# Battery_Mgmt_Sys_-_AMS.net
KiCad netlist of a schematic drawn in Altium Designer
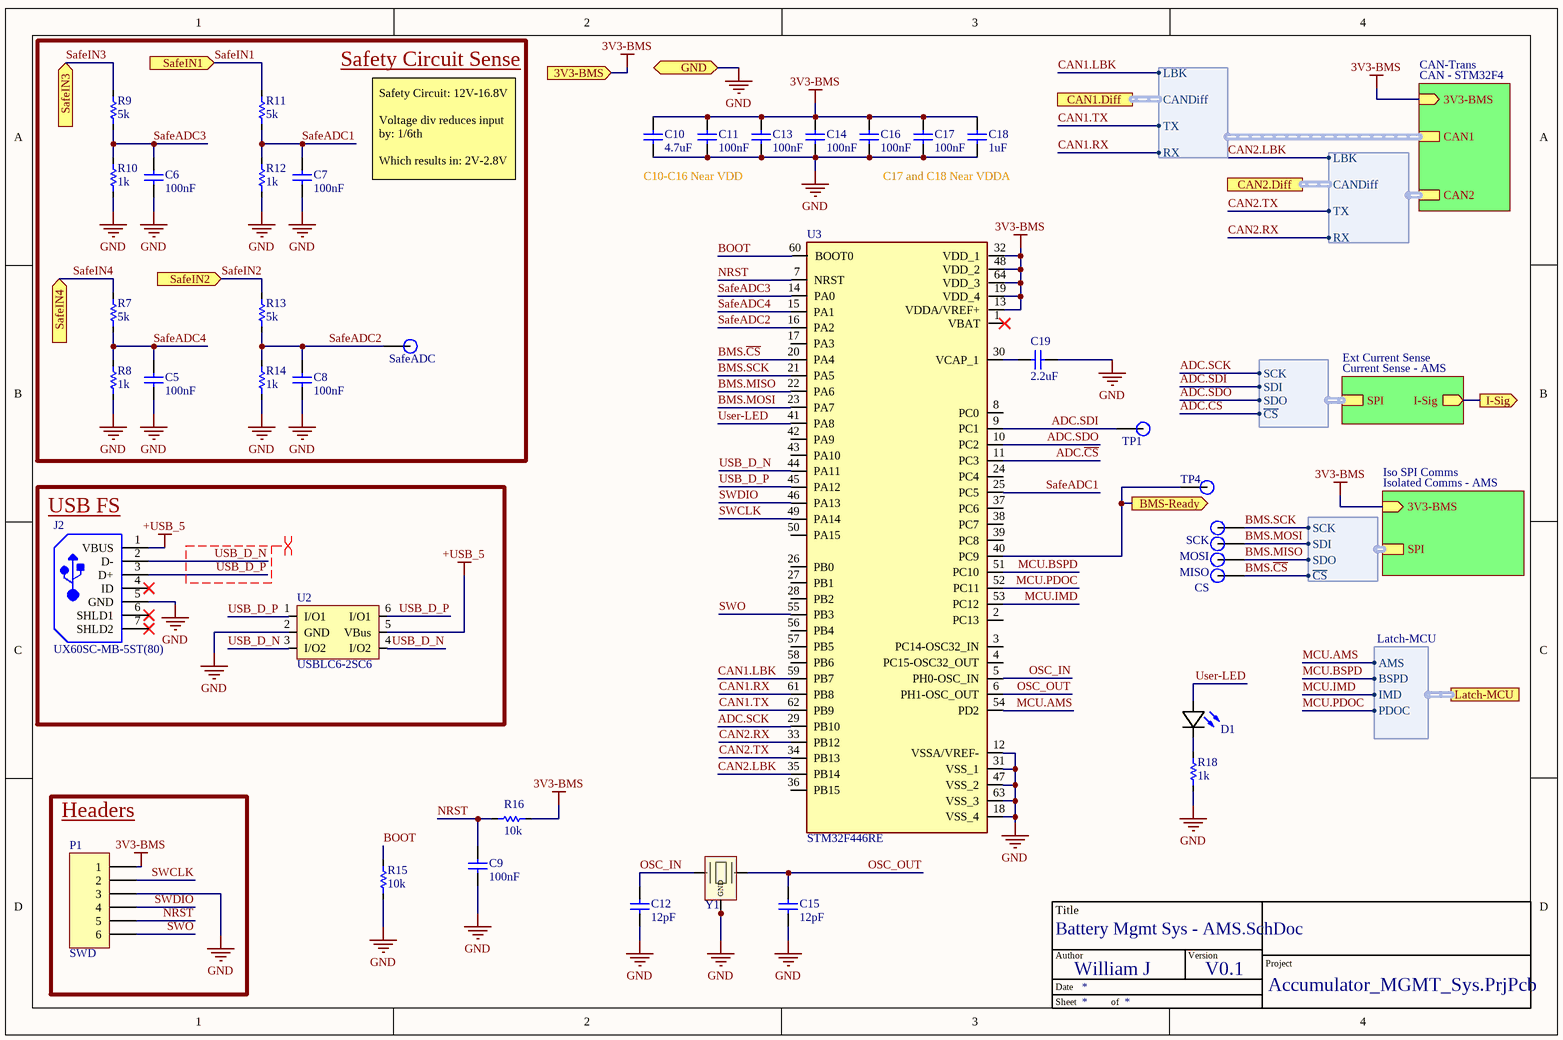
[diagram p0: Battery Mgmt Sys - AMS.SchDoc]

(export (version "E")
  (design (tool "Eeschema 10.0.6"))
  (components
    (comp (ref "C5")
      (value "100nF")
      (footprint "C_0603")
      (description "Capacitor")
      (fields (field (name "Comment") "C0603C104K3RAC7013"))
      (libsource (lib "Passives") (part "Capacitor"))
    )
    (comp (ref "C6")
      (value "100nF")
      (footprint "C_0603")
      (description "Capacitor")
      (fields (field (name "Comment") "C0603C104K3RAC7013"))
      (libsource (lib "Passives") (part "Capacitor"))
    )
    (comp (ref "C7")
      (value "100nF")
      (footprint "C_0603")
      (description "Capacitor")
      (fields (field (name "Comment") "C0603C104K3RAC7013"))
      (libsource (lib "Passives") (part "Capacitor"))
    )
    (comp (ref "C8")
      (value "100nF")
      (footprint "C_0603")
      (description "Capacitor")
      (fields (field (name "Comment") "C0603C104K3RAC7013"))
      (libsource (lib "Passives") (part "Capacitor"))
    )
    (comp (ref "C9")
      (value "100nF")
      (footprint "C_0603")
      (description "Capacitor")
      (fields (field (name "Comment") "C0603C104K3RAC7013"))
      (libsource (lib "Passives") (part "Capacitor"))
    )
    (comp (ref "C10")
      (value "4.7uF")
      (footprint "C_0603")
      (description "Capacitor")
      (fields (field (name "Comment") "CL10A475KP8NNNL"))
      (libsource (lib "Passives") (part "Capacitor"))
    )
    (comp (ref "C11")
      (value "100nF")
      (footprint "C_0603")
      (description "Capacitor")
      (fields (field (name "Comment") "C0603C104K3RAC7013"))
      (libsource (lib "Passives") (part "Capacitor"))
    )
    (comp (ref "C12")
      (value "12pF")
      (footprint "0402")
      (description "Capacitor")
      (fields (field (name "Comment") "GCM1555C1H120FA16D"))
      (libsource (lib "Passives") (part "Capacitor"))
    )
    (comp (ref "C13")
      (value "100nF")
      (footprint "C_0603")
      (description "Capacitor")
      (fields (field (name "Comment") "C0603C104K3RAC7013"))
      (libsource (lib "Passives") (part "Capacitor"))
    )
    (comp (ref "C14")
      (value "100nF")
      (footprint "C_0603")
      (description "Capacitor")
      (fields (field (name "Comment") "C0603C104K3RAC7013"))
      (libsource (lib "Passives") (part "Capacitor"))
    )
    (comp (ref "C15")
      (value "12pF")
      (footprint "0402")
      (description "Capacitor")
      (fields (field (name "Comment") "GCM1555C1H120FA16D"))
      (libsource (lib "Passives") (part "Capacitor"))
    )
    (comp (ref "C16")
      (value "100nF")
      (footprint "C_0603")
      (description "Capacitor")
      (fields (field (name "Comment") "C0603C104K3RAC7013"))
      (libsource (lib "Passives") (part "Capacitor"))
    )
    (comp (ref "C17")
      (value "100nF")
      (footprint "C_0603")
      (description "Capacitor")
      (fields (field (name "Comment") "C0603C104K3RAC7013"))
      (libsource (lib "Passives") (part "Capacitor"))
    )
    (comp (ref "C18")
      (value "1uF")
      (footprint "C_0603")
      (description "Capacitor")
      (fields (field (name "Comment") "CL10A105KP8NNNL"))
      (libsource (lib "Passives") (part "Capacitor"))
    )
    (comp (ref "C19")
      (value "2.2uF")
      (footprint "C_0603")
      (description "Capacitor")
      (fields (field (name "Comment") "CL10A225KP8NNNC"))
      (libsource (lib "Passives") (part "Capacitor"))
    )
    (comp (ref "CS")
      (value "Test Point")
      (footprint "Test Point")
      (description "1.2mm Test point")
      (libsource (lib "PCHLib") (part "Test Point"))
    )
    (comp (ref "D1")
      (value "150060BS55040")
      (footprint "LED (0603)")
      (description "LED BLUE DIFFUSED 0603 SMD")
      (fields (field (name "MANUFACTURER") "Wurth Electronics"))
      (libsource (lib "LEDLib") (part "150060BS55040"))
    )
    (comp (ref "J2")
      (value "UX60SC-MB-5ST(80)")
      (footprint "HIRO-UX60SC-MB-5ST(80)_V")
      (fields (field (name "MANUFACTURER") "Hirose Electric"))
      (libsource (lib "Altium Content Vault") (part "USB-5-2SHLD"))
    )
    (comp (ref "MISO")
      (value "Test Point")
      (footprint "Test Point")
      (description "1.2mm Test point")
      (libsource (lib "PCHLib") (part "Test Point"))
    )
    (comp (ref "MOSI")
      (value "Test Point")
      (footprint "Test Point")
      (description "1.2mm Test point")
      (libsource (lib "PCHLib") (part "Test Point"))
    )
    (comp (ref "P1")
      (value "SWD")
      (footprint "HDR1X6")
      (description "Header, 6-Pin")
      (fields (field (name "PUBLISHER") "Altium Limited"))
      (libsource (lib "Miscellaneous Connectors") (part "Header 6"))
    )
    (comp (ref "R7")
      (value "5k")
      (footprint "R-0603")
      (fields (field (name "Comment") "CR0603AFX-5101EAS"))
      (libsource (lib "Passives") (part "Resistor"))
    )
    (comp (ref "R8")
      (value "1k")
      (footprint "R-0603")
      (description "Voltage divider")
      (fields (field (name "Comment") "CR0603AFX-1001ELF"))
      (libsource (lib "Passives") (part "Resistor"))
    )
    (comp (ref "R9")
      (value "5k")
      (footprint "R-0603")
      (fields (field (name "Comment") "CR0603AFX-5101EAS"))
      (libsource (lib "Passives") (part "Resistor"))
    )
    (comp (ref "R10")
      (value "1k")
      (footprint "R-0603")
      (description "Voltage divider")
      (fields (field (name "Comment") "CR0603AFX-1001ELF"))
      (libsource (lib "Passives") (part "Resistor"))
    )
    (comp (ref "R11")
      (value "5k")
      (footprint "R-0603")
      (fields (field (name "Comment") "CR0603AFX-5101EAS"))
      (libsource (lib "Passives") (part "Resistor"))
    )
    (comp (ref "R12")
      (value "1k")
      (footprint "R-0603")
      (description "Voltage divider")
      (fields (field (name "Comment") "CR0603AFX-1001ELF"))
      (libsource (lib "Passives") (part "Resistor"))
    )
    (comp (ref "R13")
      (value "5k")
      (footprint "R-0603")
      (fields (field (name "Comment") "CR0603AFX-5101EAS"))
      (libsource (lib "Passives") (part "Resistor"))
    )
    (comp (ref "R14")
      (value "1k")
      (footprint "R-0603")
      (description "Voltage divider")
      (fields (field (name "Comment") "CR0603AFX-1001ELF"))
      (libsource (lib "Passives") (part "Resistor"))
    )
    (comp (ref "R15")
      (value "10k")
      (footprint "R-0603")
      (description "Resistor")
      (fields (field (name "Comment") "RC0603FR-1310KL"))
      (libsource (lib "Passives") (part "Resistor"))
    )
    (comp (ref "R16")
      (value "10k")
      (footprint "R-0603")
      (description "Resistor")
      (fields (field (name "Comment") "RC0603FR-1310KL"))
      (libsource (lib "Passives") (part "Resistor"))
    )
    (comp (ref "R18")
      (value "1k")
      (footprint "R-0603")
      (description "Resistor")
      (fields (field (name "Comment") "CR0603AFX-1001ELF"))
      (libsource (lib "Passives") (part "Resistor"))
    )
    (comp (ref "SafeADC")
      (value "Test Point")
      (footprint "Test Point")
      (description "1.2mm Test point")
      (libsource (lib "PCHLib") (part "Test Point"))
    )
    (comp (ref "SCK")
      (value "Test Point")
      (footprint "Test Point")
      (description "1.2mm Test point")
      (libsource (lib "PCHLib") (part "Test Point"))
    )
    (comp (ref "TP1")
      (value "Test Point")
      (footprint "Test Point")
      (description "1.2mm Test point")
      (libsource (lib "PCHLib") (part "Test Point"))
    )
    (comp (ref "TP4")
      (value "Test Point")
      (footprint "Test Point")
      (description "1.2mm Test point")
      (libsource (lib "PCHLib") (part "Test Point"))
    )
    (comp (ref "U2")
      (value "USBLC6-2SC6")
      (footprint "USBLC6-2SC6")
      (description "TVS DIODE 5.25V 17V SOT23-6")
      (fields (field (name "MANUFACTURER") "STMicroelectronics"))
      (libsource (lib "CompLib") (part "USBLC6-2SC6"))
    )
    (comp (ref "U3")
      (value "STM32F446RE")
      (footprint "QFP50P1200X1200X160-64N")
      (description "32 Bit Microcontroller, High Performance, ARM Cortex-M4, 180 MHz, 256 KB, 128 KB, 64, LQFP")
      (libsource (lib "SnapEDA_Library") (part "STM32F446RE"))
    )
    (comp (ref "Y1")
      (value "CX2016DB26000D0FLJCC")
      (footprint "CX2016DB26000D0FLJCC")
      (description "Crystals AEC-Q200 26000kHz 8pF 2x1.6mm")
      (libsource (lib "PCHLib") (part "CX2016DB26000D0FLJCC"))
    )
  )
  (nets
    (net (code "5") (name "+USB_5") (class "Default")
      (node (ref "J2") (pin "1") (pinfunction "VBUS_1") (pintype "passive"))
      (node (ref "U2") (pin "5") (pinfunction "VBus_5") (pintype "passive"))
    )
    (net (code "7") (name "/ADC.SCK") (class "Default")
      (node (ref "U3") (pin "29") (pinfunction "PB10_29") (pintype "passive"))
    )
    (net (code "8") (name "/ADC.SDI") (class "Default")
      (node (ref "TP1") (pin "1") (pinfunction "1_1") (pintype "passive"))
      (node (ref "U3") (pin "9") (pinfunction "PC1_9") (pintype "passive"))
    )
    (net (code "9") (name "/ADC.SDO") (class "Default")
      (node (ref "U3") (pin "10") (pinfunction "PC2_10") (pintype "passive"))
    )
    (net (code "10") (name "/ADC.~{CS}") (class "Default")
      (node (ref "U3") (pin "11") (pinfunction "PC3_11") (pintype "passive"))
    )
    (net (code "11") (name "/BMS-Ready") (class "Default")
      (node (ref "TP4") (pin "1") (pinfunction "1_1") (pintype "passive"))
      (node (ref "U3") (pin "40") (pinfunction "PC9_40") (pintype "passive"))
    )
    (net (code "12") (name "/BMS.MISO") (class "Default")
      (node (ref "MISO") (pin "1") (pinfunction "1_1") (pintype "passive"))
      (node (ref "U3") (pin "22") (pinfunction "PA6_22") (pintype "passive"))
    )
    (net (code "13") (name "/BMS.MOSI") (class "Default")
      (node (ref "MOSI") (pin "1") (pinfunction "1_1") (pintype "passive"))
      (node (ref "U3") (pin "23") (pinfunction "PA7_23") (pintype "passive"))
    )
    (net (code "14") (name "/BMS.SCK") (class "Default")
      (node (ref "SCK") (pin "1") (pinfunction "1_1") (pintype "passive"))
      (node (ref "U3") (pin "21") (pinfunction "PA5_21") (pintype "passive"))
    )
    (net (code "15") (name "/BMS.~{CS}") (class "Default")
      (node (ref "CS") (pin "1") (pinfunction "1_1") (pintype "passive"))
      (node (ref "U3") (pin "20") (pinfunction "PA4_20") (pintype "passive"))
    )
    (net (code "16") (name "/BOOT") (class "Default")
      (node (ref "R15") (pin "2") (pinfunction "2_2") (pintype "passive"))
      (node (ref "U3") (pin "60") (pinfunction "BOOT0_60") (pintype "passive"))
    )
    (net (code "17") (name "/CAN1.LBK") (class "Default")
      (node (ref "U3") (pin "59") (pinfunction "PB7_59") (pintype "passive"))
    )
    (net (code "18") (name "/CAN1.RX") (class "Default")
      (node (ref "U3") (pin "61") (pinfunction "PB8_61") (pintype "passive"))
    )
    (net (code "19") (name "/CAN1.TX") (class "Default")
      (node (ref "U3") (pin "62") (pinfunction "PB9_62") (pintype "passive"))
    )
    (net (code "22") (name "/CAN2.LBK") (class "Default")
      (node (ref "U3") (pin "35") (pinfunction "PB14_35") (pintype "passive"))
    )
    (net (code "23") (name "/CAN2.RX") (class "Default")
      (node (ref "U3") (pin "33") (pinfunction "PB12_33") (pintype "passive"))
    )
    (net (code "24") (name "/CAN2.TX") (class "Default")
      (node (ref "U3") (pin "34") (pinfunction "PB13_34") (pintype "passive"))
    )
    (net (code "26") (name "/MCU.AMS") (class "Default")
      (node (ref "U3") (pin "54") (pinfunction "PD2_54") (pintype "passive"))
    )
    (net (code "27") (name "/MCU.BSPD") (class "Default")
      (node (ref "U3") (pin "51") (pinfunction "PC10_51") (pintype "passive"))
    )
    (net (code "28") (name "/MCU.IMD") (class "Default")
      (node (ref "U3") (pin "53") (pinfunction "PC12_53") (pintype "passive"))
    )
    (net (code "29") (name "/MCU.PDOC") (class "Default")
      (node (ref "U3") (pin "52") (pinfunction "PC11_52") (pintype "passive"))
    )
    (net (code "30") (name "/NRST") (class "Default")
      (node (ref "C9") (pin "2") (pinfunction "2_2") (pintype "passive"))
      (node (ref "P1") (pin "5") (pinfunction "5_5") (pintype "passive"))
      (node (ref "R16") (pin "1") (pinfunction "1_1") (pintype "passive"))
      (node (ref "U3") (pin "7") (pinfunction "NRST_7") (pintype "passive"))
    )
    (net (code "31") (name "/OSC_IN") (class "Default")
      (node (ref "C12") (pin "2") (pinfunction "2_2") (pintype "passive"))
      (node (ref "U3") (pin "5") (pinfunction "PH0-OSC_IN_5") (pintype "passive"))
      (node (ref "Y1") (pin "1") (pinfunction "1_1") (pintype "passive"))
    )
    (net (code "32") (name "/OSC_OUT") (class "Default")
      (node (ref "C15") (pin "2") (pinfunction "2_2") (pintype "passive"))
      (node (ref "U3") (pin "6") (pinfunction "PH1-OSC_OUT_6") (pintype "passive"))
      (node (ref "Y1") (pin "3") (pinfunction "3_3") (pintype "passive"))
    )
    (net (code "33") (name "/SWCLK") (class "Default")
      (node (ref "P1") (pin "2") (pinfunction "2_2") (pintype "passive"))
      (node (ref "U3") (pin "49") (pinfunction "PA14_49") (pintype "passive"))
    )
    (net (code "34") (name "/SWDIO") (class "Default")
      (node (ref "P1") (pin "4") (pinfunction "4_4") (pintype "passive"))
      (node (ref "U3") (pin "46") (pinfunction "PA13_46") (pintype "passive"))
    )
    (net (code "35") (name "/SWO") (class "Default")
      (node (ref "P1") (pin "6") (pinfunction "6_6") (pintype "passive"))
      (node (ref "U3") (pin "55") (pinfunction "PB3_55") (pintype "passive"))
    )
    (net (code "36") (name "/SafeADC1") (class "Default")
      (node (ref "C7") (pin "2") (pinfunction "2_2") (pintype "passive"))
      (node (ref "R11") (pin "1") (pinfunction "1_1") (pintype "passive"))
      (node (ref "R12") (pin "2") (pinfunction "2_2") (pintype "passive"))
      (node (ref "U3") (pin "25") (pinfunction "PC5_25") (pintype "passive"))
    )
    (net (code "37") (name "/SafeADC2") (class "Default")
      (node (ref "C8") (pin "2") (pinfunction "2_2") (pintype "passive"))
      (node (ref "R13") (pin "1") (pinfunction "1_1") (pintype "passive"))
      (node (ref "R14") (pin "2") (pinfunction "2_2") (pintype "passive"))
      (node (ref "SafeADC") (pin "1") (pinfunction "1_1") (pintype "passive"))
      (node (ref "U3") (pin "16") (pinfunction "PA2_16") (pintype "passive"))
    )
    (net (code "38") (name "/SafeADC3") (class "Default")
      (node (ref "C6") (pin "2") (pinfunction "2_2") (pintype "passive"))
      (node (ref "R10") (pin "2") (pinfunction "2_2") (pintype "passive"))
      (node (ref "R9") (pin "1") (pinfunction "1_1") (pintype "passive"))
      (node (ref "U3") (pin "14") (pinfunction "PA0_14") (pintype "passive"))
    )
    (net (code "39") (name "/SafeADC4") (class "Default")
      (node (ref "C5") (pin "2") (pinfunction "2_2") (pintype "passive"))
      (node (ref "R7") (pin "1") (pinfunction "1_1") (pintype "passive"))
      (node (ref "R8") (pin "2") (pinfunction "2_2") (pintype "passive"))
      (node (ref "U3") (pin "15") (pinfunction "PA1_15") (pintype "passive"))
    )
    (net (code "40") (name "/SafeIN1") (class "Default")
      (node (ref "R11") (pin "2") (pinfunction "2_2") (pintype "passive"))
    )
    (net (code "41") (name "/SafeIN2") (class "Default")
      (node (ref "R13") (pin "2") (pinfunction "2_2") (pintype "passive"))
    )
    (net (code "42") (name "/SafeIN3") (class "Default")
      (node (ref "R9") (pin "2") (pinfunction "2_2") (pintype "passive"))
    )
    (net (code "43") (name "/SafeIN4") (class "Default")
      (node (ref "R7") (pin "2") (pinfunction "2_2") (pintype "passive"))
    )
    (net (code "44") (name "/USB_D_N") (class "Default")
      (node (ref "J2") (pin "2") (pinfunction "D-_2") (pintype "passive"))
      (node (ref "U2") (pin "3") (pinfunction "I/O2_3") (pintype "passive"))
      (node (ref "U2") (pin "4") (pinfunction "I/O2_4") (pintype "passive"))
      (node (ref "U3") (pin "44") (pinfunction "PA11_44") (pintype "passive"))
    )
    (net (code "45") (name "/USB_D_P") (class "Default")
      (node (ref "J2") (pin "3") (pinfunction "D+_3") (pintype "passive"))
      (node (ref "U2") (pin "1") (pinfunction "I/O1_1") (pintype "passive"))
      (node (ref "U2") (pin "6") (pinfunction "I/O1_6") (pintype "passive"))
      (node (ref "U3") (pin "45") (pinfunction "PA12_45") (pintype "passive"))
    )
    (net (code "46") (name "/User-LED") (class "Default")
      (node (ref "D1") (pin "2") (pinfunction "A_2") (pintype "passive"))
      (node (ref "U3") (pin "41") (pinfunction "PA8_41") (pintype "passive"))
    )
    (net (code "50") (name "3V3-BMS") (class "Default")
      (node (ref "C10") (pin "2") (pinfunction "2_2") (pintype "passive"))
      (node (ref "C11") (pin "2") (pinfunction "2_2") (pintype "passive"))
      (node (ref "C13") (pin "2") (pinfunction "2_2") (pintype "passive"))
      (node (ref "C14") (pin "2") (pinfunction "2_2") (pintype "passive"))
      (node (ref "C16") (pin "2") (pinfunction "2_2") (pintype "passive"))
      (node (ref "C17") (pin "2") (pinfunction "2_2") (pintype "passive"))
      (node (ref "C18") (pin "2") (pinfunction "2_2") (pintype "passive"))
      (node (ref "P1") (pin "1") (pinfunction "1_1") (pintype "passive"))
      (node (ref "R16") (pin "2") (pinfunction "2_2") (pintype "passive"))
      (node (ref "U3") (pin "13") (pinfunction "VDDA/VREF+_13") (pintype "passive"))
      (node (ref "U3") (pin "19") (pinfunction "VDD_4_19") (pintype "passive"))
      (node (ref "U3") (pin "32") (pinfunction "VDD_1_32") (pintype "passive"))
      (node (ref "U3") (pin "48") (pinfunction "VDD_2_48") (pintype "passive"))
      (node (ref "U3") (pin "64") (pinfunction "VDD_3_64") (pintype "passive"))
    )
    (net (code "51") (name "GND") (class "Default")
      (node (ref "C10") (pin "1") (pinfunction "1_1") (pintype "passive"))
      (node (ref "C11") (pin "1") (pinfunction "1_1") (pintype "passive"))
      (node (ref "C12") (pin "1") (pinfunction "1_1") (pintype "passive"))
      (node (ref "C13") (pin "1") (pinfunction "1_1") (pintype "passive"))
      (node (ref "C14") (pin "1") (pinfunction "1_1") (pintype "passive"))
      (node (ref "C15") (pin "1") (pinfunction "1_1") (pintype "passive"))
      (node (ref "C16") (pin "1") (pinfunction "1_1") (pintype "passive"))
      (node (ref "C17") (pin "1") (pinfunction "1_1") (pintype "passive"))
      (node (ref "C18") (pin "1") (pinfunction "1_1") (pintype "passive"))
      (node (ref "C19") (pin "1") (pinfunction "1_1") (pintype "passive"))
      (node (ref "C5") (pin "1") (pinfunction "1_1") (pintype "passive"))
      (node (ref "C6") (pin "1") (pinfunction "1_1") (pintype "passive"))
      (node (ref "C7") (pin "1") (pinfunction "1_1") (pintype "passive"))
      (node (ref "C8") (pin "1") (pinfunction "1_1") (pintype "passive"))
      (node (ref "C9") (pin "1") (pinfunction "1_1") (pintype "passive"))
      (node (ref "J2") (pin "5") (pinfunction "GND_5") (pintype "passive"))
      (node (ref "P1") (pin "3") (pinfunction "3_3") (pintype "passive"))
      (node (ref "R10") (pin "1") (pinfunction "1_1") (pintype "passive"))
      (node (ref "R12") (pin "1") (pinfunction "1_1") (pintype "passive"))
      (node (ref "R14") (pin "1") (pinfunction "1_1") (pintype "passive"))
      (node (ref "R15") (pin "1") (pinfunction "1_1") (pintype "passive"))
      (node (ref "R18") (pin "1") (pinfunction "1_1") (pintype "passive"))
      (node (ref "R8") (pin "1") (pinfunction "1_1") (pintype "passive"))
      (node (ref "U2") (pin "2") (pinfunction "GND_2") (pintype "passive"))
      (node (ref "U3") (pin "12") (pinfunction "VSSA/VREF-_12") (pintype "passive"))
      (node (ref "U3") (pin "18") (pinfunction "VSS_4_18") (pintype "passive"))
      (node (ref "U3") (pin "31") (pinfunction "VSS_1_31") (pintype "passive"))
      (node (ref "U3") (pin "47") (pinfunction "VSS_2_47") (pintype "passive"))
      (node (ref "U3") (pin "63") (pinfunction "VSS_3_63") (pintype "passive"))
      (node (ref "Y1") (pin "2") (pinfunction "GND_2") (pintype "passive"))
      (node (ref "Y1") (pin "4") (pinfunction "GND_4") (pintype "passive"))
    )
    (net (code "52") (name "Net-(D1-K)") (class "Default")
      (node (ref "D1") (pin "1") (pinfunction "K_1") (pintype "passive"))
      (node (ref "R18") (pin "2") (pinfunction "2_2") (pintype "passive"))
    )
    (net (code "53") (name "Net-(U3-VCAP_1)") (class "Default")
      (node (ref "C19") (pin "2") (pinfunction "2_2") (pintype "passive"))
      (node (ref "U3") (pin "30") (pinfunction "VCAP_1_30") (pintype "passive"))
    )
    (net (code "54") (name "unconnected-(J2-ID-Pad4)") (class "Default")
      (node (ref "J2") (pin "4") (pinfunction "ID_4") (pintype "passive+no_connect"))
    )
    (net (code "55") (name "unconnected-(J2-SHLD1-Pad6)") (class "Default")
      (node (ref "J2") (pin "6") (pinfunction "SHLD1_6") (pintype "passive+no_connect"))
    )
    (net (code "56") (name "unconnected-(J2-SHLD2-Pad7)") (class "Default")
      (node (ref "J2") (pin "7") (pinfunction "SHLD2_7") (pintype "passive+no_connect"))
    )
    (net (code "57") (name "unconnected-(U3-PA3-Pad17)") (class "Default")
      (node (ref "U3") (pin "17") (pinfunction "PA3_17") (pintype "passive"))
    )
    (net (code "58") (name "unconnected-(U3-PA9-Pad42)") (class "Default")
      (node (ref "U3") (pin "42") (pinfunction "PA9_42") (pintype "passive"))
    )
    (net (code "59") (name "unconnected-(U3-PA10-Pad43)") (class "Default")
      (node (ref "U3") (pin "43") (pinfunction "PA10_43") (pintype "passive"))
    )
    (net (code "60") (name "unconnected-(U3-PA15-Pad50)") (class "Default")
      (node (ref "U3") (pin "50") (pinfunction "PA15_50") (pintype "passive"))
    )
    (net (code "61") (name "unconnected-(U3-PB0-Pad26)") (class "Default")
      (node (ref "U3") (pin "26") (pinfunction "PB0_26") (pintype "passive"))
    )
    (net (code "62") (name "unconnected-(U3-PB1-Pad27)") (class "Default")
      (node (ref "U3") (pin "27") (pinfunction "PB1_27") (pintype "passive"))
    )
    (net (code "63") (name "unconnected-(U3-PB2-Pad28)") (class "Default")
      (node (ref "U3") (pin "28") (pinfunction "PB2_28") (pintype "passive"))
    )
    (net (code "64") (name "unconnected-(U3-PB4-Pad56)") (class "Default")
      (node (ref "U3") (pin "56") (pinfunction "PB4_56") (pintype "passive"))
    )
    (net (code "65") (name "unconnected-(U3-PB5-Pad57)") (class "Default")
      (node (ref "U3") (pin "57") (pinfunction "PB5_57") (pintype "passive"))
    )
    (net (code "66") (name "unconnected-(U3-PB6-Pad58)") (class "Default")
      (node (ref "U3") (pin "58") (pinfunction "PB6_58") (pintype "passive"))
    )
    (net (code "67") (name "unconnected-(U3-PB15-Pad36)") (class "Default")
      (node (ref "U3") (pin "36") (pinfunction "PB15_36") (pintype "passive"))
    )
    (net (code "68") (name "unconnected-(U3-PC0-Pad8)") (class "Default")
      (node (ref "U3") (pin "8") (pinfunction "PC0_8") (pintype "passive"))
    )
    (net (code "69") (name "unconnected-(U3-PC4-Pad24)") (class "Default")
      (node (ref "U3") (pin "24") (pinfunction "PC4_24") (pintype "passive"))
    )
    (net (code "70") (name "unconnected-(U3-PC6-Pad37)") (class "Default")
      (node (ref "U3") (pin "37") (pinfunction "PC6_37") (pintype "passive"))
    )
    (net (code "71") (name "unconnected-(U3-PC7-Pad38)") (class "Default")
      (node (ref "U3") (pin "38") (pinfunction "PC7_38") (pintype "passive"))
    )
    (net (code "72") (name "unconnected-(U3-PC8-Pad39)") (class "Default")
      (node (ref "U3") (pin "39") (pinfunction "PC8_39") (pintype "passive"))
    )
    (net (code "73") (name "unconnected-(U3-PC13-Pad2)") (class "Default")
      (node (ref "U3") (pin "2") (pinfunction "PC13_2") (pintype "passive"))
    )
    (net (code "74") (name "unconnected-(U3-PC14-OSC32_IN-Pad3)") (class "Default")
      (node (ref "U3") (pin "3") (pinfunction "PC14-OSC32_IN_3") (pintype "passive"))
    )
    (net (code "75") (name "unconnected-(U3-PC15-OSC32_OUT-Pad4)") (class "Default")
      (node (ref "U3") (pin "4") (pinfunction "PC15-OSC32_OUT_4") (pintype "passive"))
    )
    (net (code "76") (name "unconnected-(U3-VBAT-Pad1)") (class "Default")
      (node (ref "U3") (pin "1") (pinfunction "VBAT_1") (pintype "passive+no_connect"))
    )
  )
)
